# DAC_Reference.net
KiCad netlist of a schematic drawn in Altium Designer
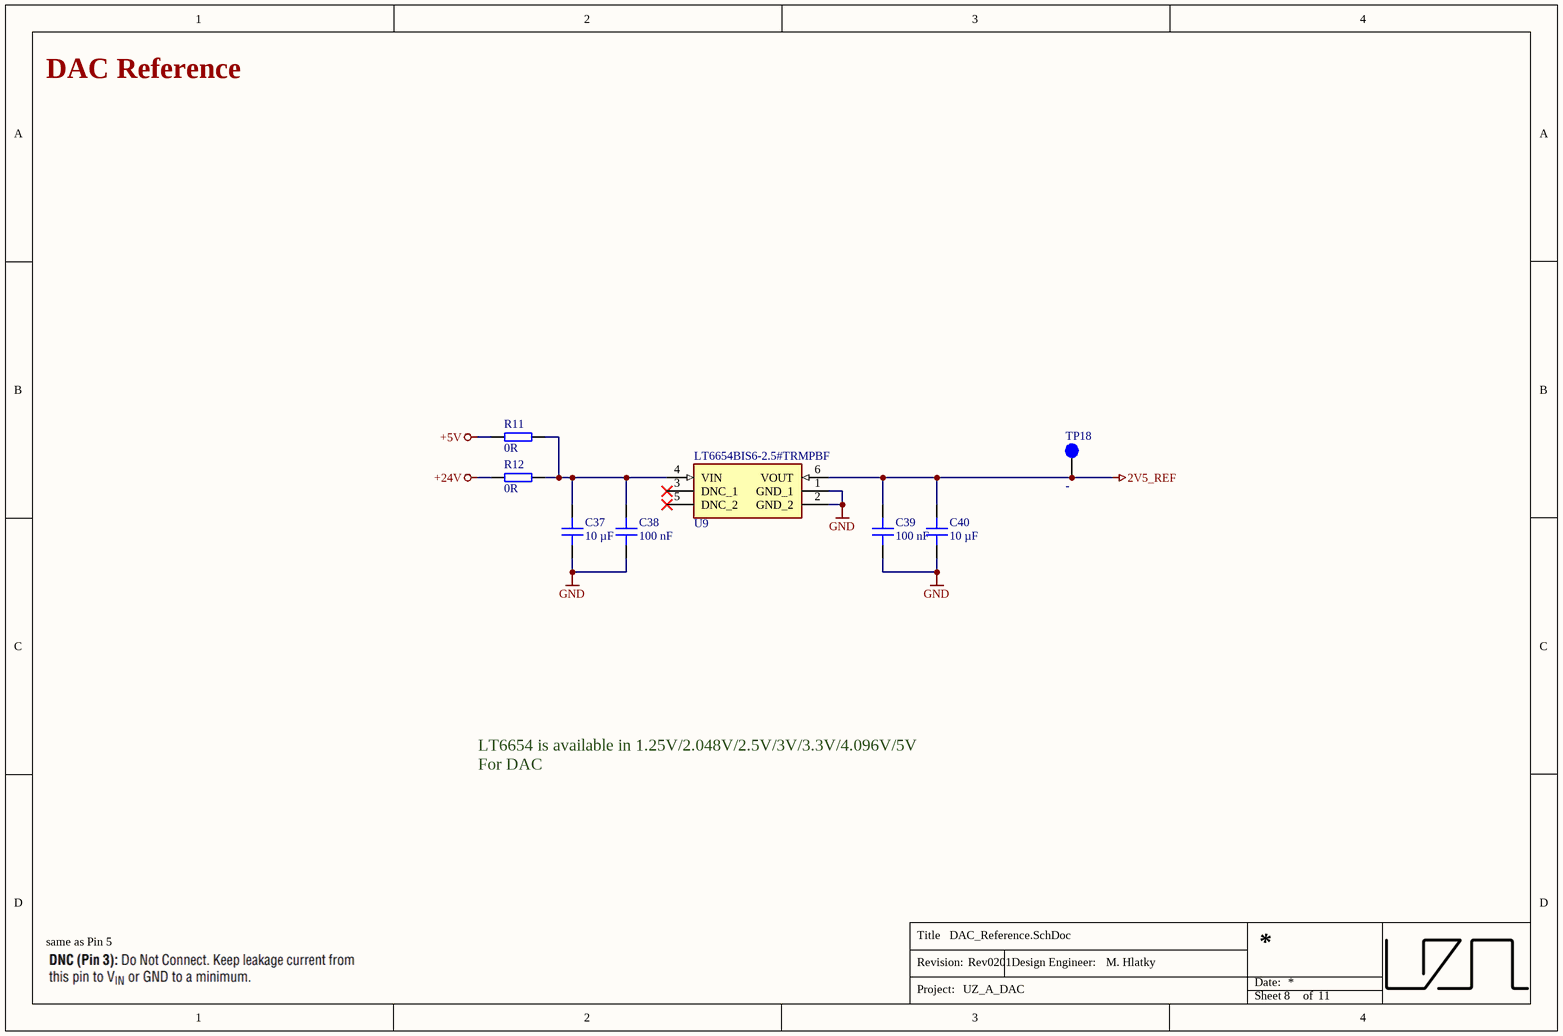
[diagram p0: DAC_Reference.SchDoc]

(export (version "E")
  (design (tool "Eeschema 10.0.6"))
  (components
    (comp (ref "C37")
      (value "10 µF")
      (footprint "C_1206")
      (description "Capacitor 1206, 50 VDC, 10 µF, X5R")
      (fields
        (field (name "MANUFACTURER PART NUMBER") "GRT31CR61H106KE01L")
        (field (name "MANUFACTURER") "Murata Electronics")
        (field (name "CREATED FROM") "MGremer")
      )
      (libsource (lib "user") (part "Capacitor"))
    )
    (comp (ref "C38")
      (value "100 nF")
      (footprint "C_0603")
      (description "Capacitor 0603, 6.3 VDC, 100 nF, X5R")
      (fields
        (field (name "MANUFACTURER PART NUMBER") "C0603C104K9PACTU")
        (field (name "MANUFACTURER") "KEMET")
        (field (name "CREATED FROM") "MGremer")
      )
      (libsource (lib "user") (part "Capacitor"))
    )
    (comp (ref "C39")
      (value "100 nF")
      (footprint "C_0603")
      (description "Capacitor 0603, 6.3 VDC, 100 nF, X5R")
      (fields
        (field (name "MANUFACTURER PART NUMBER") "C0603C104K9PACTU")
        (field (name "MANUFACTURER") "KEMET")
        (field (name "CREATED FROM") "MGremer")
      )
      (libsource (lib "user") (part "Capacitor"))
    )
    (comp (ref "C40")
      (value "10 µF")
      (footprint "C_1206")
      (description "Capacitor 1206, 50 VDC, 10 µF, X5R")
      (fields
        (field (name "MANUFACTURER PART NUMBER") "GRT31CR61H106KE01L")
        (field (name "MANUFACTURER") "Murata Electronics")
        (field (name "CREATED FROM") "MGremer")
      )
      (libsource (lib "user") (part "Capacitor"))
    )
    (comp (ref "R11")
      (value "0R")
      (footprint "RES 0603_1608")
      (description "SMD resistor E24 series")
      (fields
        (field (name "MANUFACTURER PART NUMBER") "RC0603JR-070RL")
        (field (name "MANUFACTURER") "YAGEO")
        (field (name "CREATED FROM") "MGremer")
      )
      (libsource (lib "user") (part "Resistor"))
    )
    (comp (ref "R12")
      (value "0R")
      (footprint "RES 0603_1608")
      (description "SMD resistor E24 series")
      (fields
        (field (name "MANUFACTURER PART NUMBER") "RC0603JR-070RL")
        (field (name "MANUFACTURER") "YAGEO")
        (field (name "CREATED FROM") "MGremer")
      )
      (libsource (lib "user") (part "Resistor"))
    )
    (comp (ref "TP18")
      (value "-")
      (footprint "TP_1mm")
      (description "Test Point 1 mm")
      (fields (field (name "CREATED") "2018_06_25_AGeiger") (field (name "CREATED FROM") "MGremer"))
      (libsource (lib "user") (part "TP_1mm"))
    )
    (comp (ref "U9")
      (value "LT6654BIS6-2.5#TRMPBF")
      (footprint "SOT95P280X100-6N")
      (description "Precision Wide Supply High Output Drive Low Noise Reference")
      (fields
        (field (name "MANUFACTURER_PART_NUMBER") "LT6654AHS6-5#TRMPBF")
        (field (name "MANUFACTURER") "Analog Devices")
        (field (name "CREATED FROM") "MHlatky")
      )
      (libsource (lib "user") (part "LT6654AHS625#TRMPBF"))
    )
  )
  (nets
    (net (code "1") (name "+5V") (class "Default")
      (node (ref "R11") (pin "1") (pinfunction "1_1") (pintype "passive"))
    )
    (net (code "2") (name "+24V") (class "Default")
      (node (ref "R12") (pin "1") (pinfunction "1_1") (pintype "passive"))
    )
    (net (code "3") (name "2V5_REF") (class "Default")
      (node (ref "C39") (pin "2") (pinfunction "2_2") (pintype "passive"))
      (node (ref "C40") (pin "2") (pinfunction "2_2") (pintype "passive"))
      (node (ref "TP18") (pin "1") (pintype "passive"))
      (node (ref "U9") (pin "6") (pinfunction "VOUT_6") (pintype "input"))
    )
    (net (code "4") (name "GND") (class "Default")
      (node (ref "C37") (pin "1") (pinfunction "1_1") (pintype "passive"))
      (node (ref "C38") (pin "1") (pinfunction "1_1") (pintype "passive"))
      (node (ref "C39") (pin "1") (pinfunction "1_1") (pintype "passive"))
      (node (ref "C40") (pin "1") (pinfunction "1_1") (pintype "passive"))
      (node (ref "U9") (pin "1") (pinfunction "GND_1_1") (pintype "power_in"))
      (node (ref "U9") (pin "2") (pinfunction "GND_2_2") (pintype "power_in"))
    )
    (net (code "5") (name "Net-(U9-VIN)") (class "Default")
      (node (ref "C37") (pin "2") (pinfunction "2_2") (pintype "passive"))
      (node (ref "C38") (pin "2") (pinfunction "2_2") (pintype "passive"))
      (node (ref "R11") (pin "2") (pinfunction "2_2") (pintype "passive"))
      (node (ref "R12") (pin "2") (pinfunction "2_2") (pintype "passive"))
      (node (ref "U9") (pin "4") (pinfunction "VIN_4") (pintype "input"))
    )
    (net (code "6") (name "unconnected-(U9-DNC_1-Pad3)") (class "Default")
      (node (ref "U9") (pin "3") (pinfunction "DNC_1_3") (pintype "passive+no_connect"))
    )
    (net (code "7") (name "unconnected-(U9-DNC_2-Pad5)") (class "Default")
      (node (ref "U9") (pin "5") (pinfunction "DNC_2_5") (pintype "passive+no_connect"))
    )
  )
)
